# Enabled-Controller-Mini.net
KiCad netlist of a schematic drawn in EAGLE
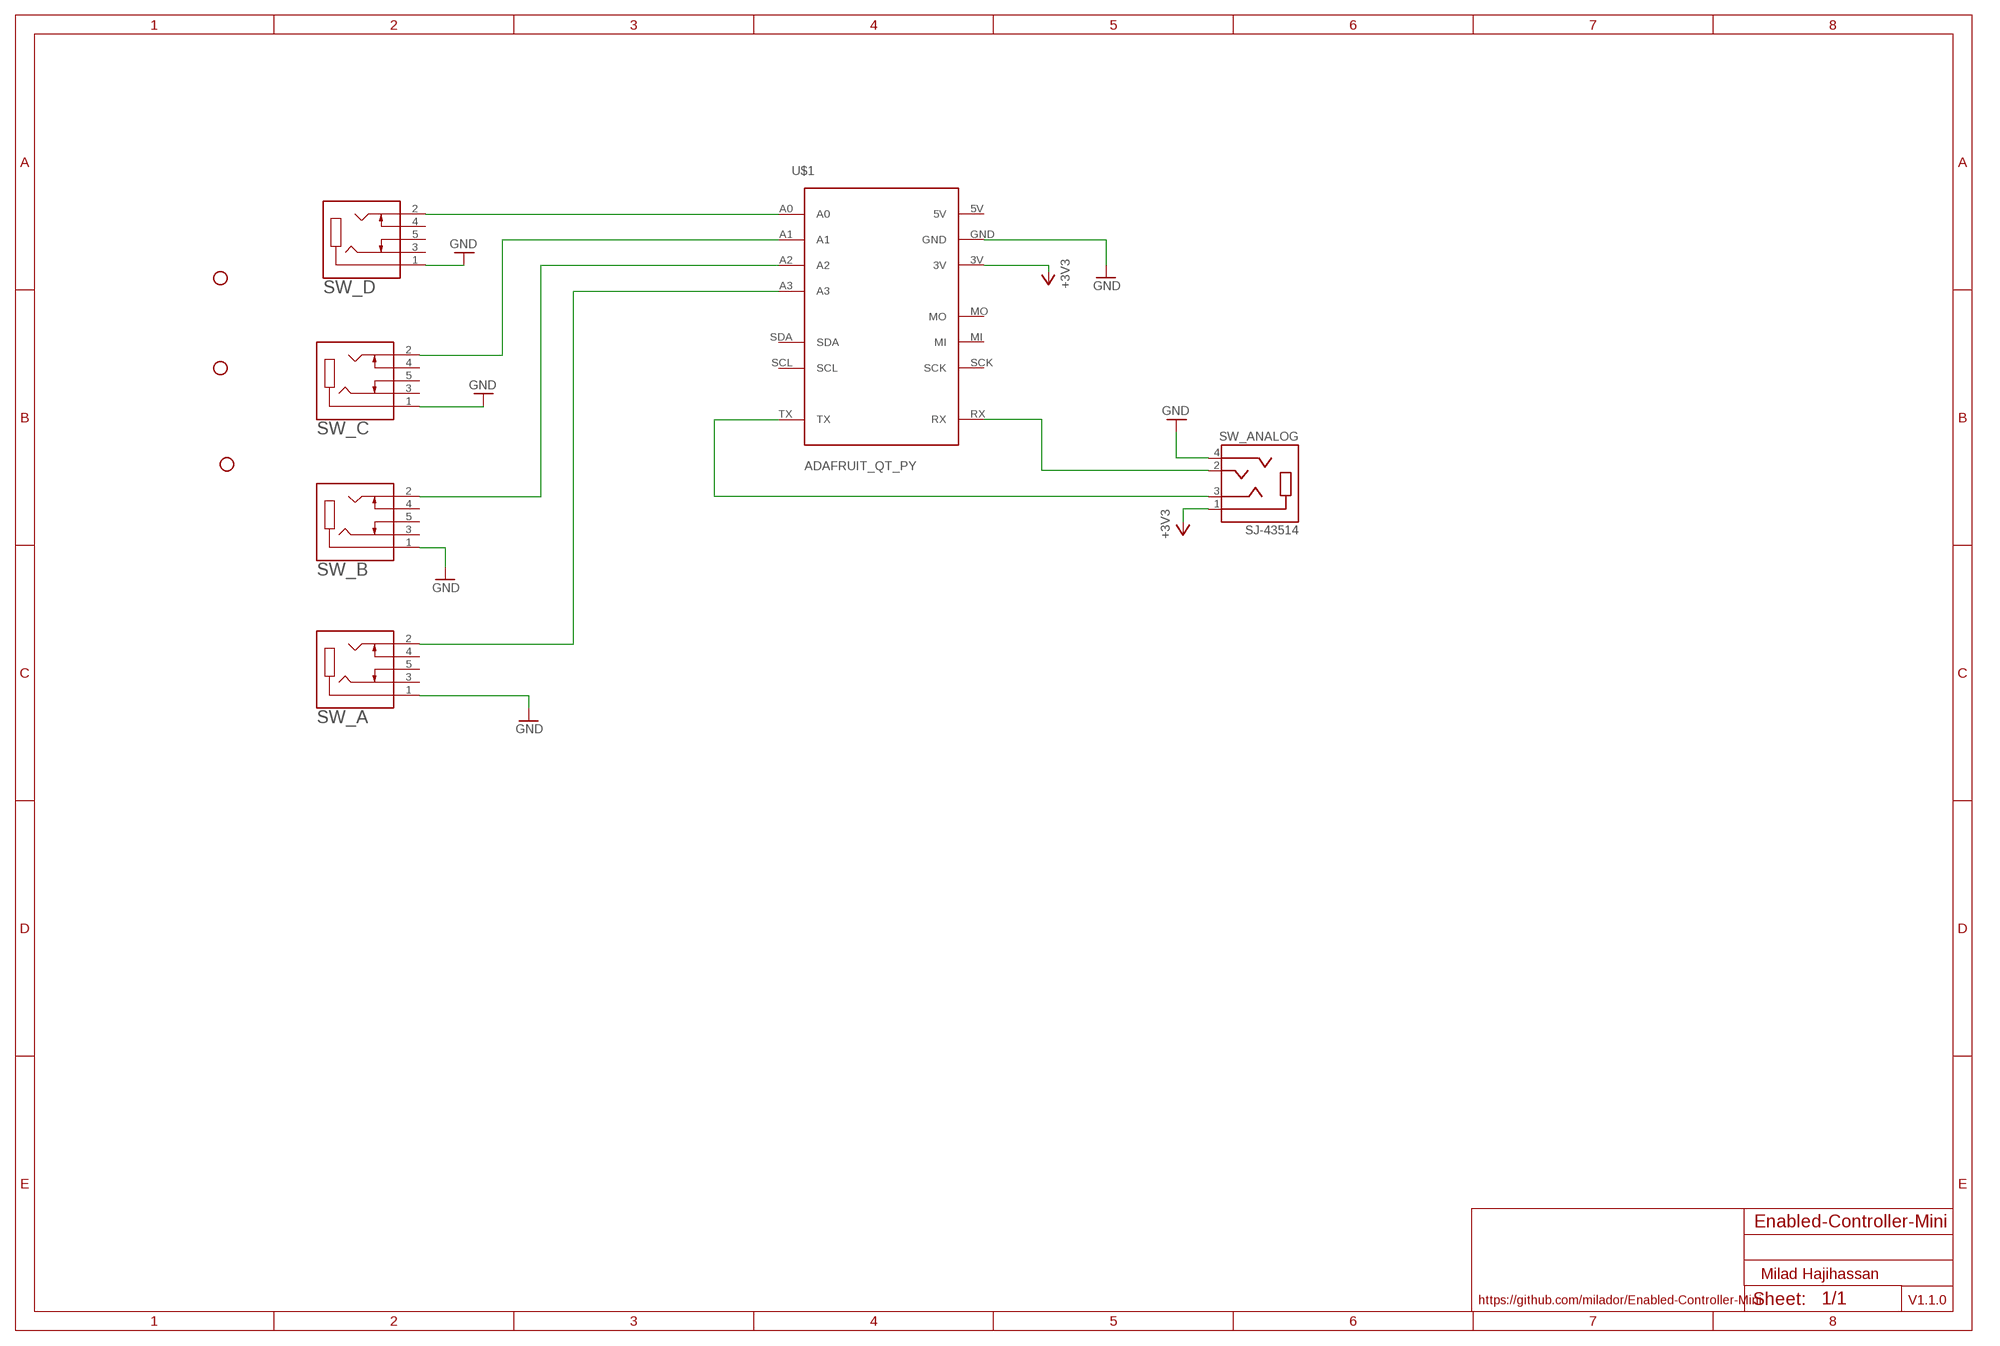
[diagram p0: schematic, sheet 1]

(export (version "E")
  (design (tool "Eeschema 10.0.6"))
  (components
    (comp (ref "STANDOFF1")
      (value "STAND-OFF-")
      (footprint "eagle-import:STAND-OFF")
      (libsource (lib "eagle-import") (part "STAND-OFF-"))
    )
    (comp (ref "STANDOFF2")
      (value "STAND-OFF-")
      (footprint "eagle-import:STAND-OFF")
      (libsource (lib "eagle-import") (part "STAND-OFF-"))
    )
    (comp (ref "STANDOFF3")
      (value "STAND-OFF-")
      (footprint "eagle-import:STAND-OFF")
      (libsource (lib "eagle-import") (part "STAND-OFF-"))
    )
    (comp (ref "SW_A")
      (value "CUI_SJ1-3535NGSJ1-3535NG")
      (footprint "eagle-import:CUI_SJ1-3535NG")
      (libsource (lib "eagle-import") (part "CUI_SJ1-3535NGSJ1-3535NG"))
    )
    (comp (ref "SW_ANALOG")
      (value "SJ-43514")
      (footprint "eagle-import:CUI_SJ-43514")
      (libsource (lib "eagle-import") (part "SJ-43514"))
    )
    (comp (ref "SW_B")
      (value "CUI_SJ1-3535NGSJ1-3535NG")
      (footprint "eagle-import:CUI_SJ1-3535NG")
      (libsource (lib "eagle-import") (part "CUI_SJ1-3535NGSJ1-3535NG"))
    )
    (comp (ref "SW_C")
      (value "CUI_SJ1-3535NGSJ1-3535NG")
      (footprint "eagle-import:CUI_SJ1-3535NG")
      (libsource (lib "eagle-import") (part "CUI_SJ1-3535NGSJ1-3535NG"))
    )
    (comp (ref "SW_D")
      (value "CUI_SJ1-3535NGSJ1-3535NG")
      (footprint "eagle-import:CUI_SJ1-3535NG")
      (libsource (lib "eagle-import") (part "CUI_SJ1-3535NGSJ1-3535NG"))
    )
    (comp (ref "U$1")
      (value "ADAFRUIT_QT_PY")
      (footprint "eagle-import:QT_PY")
      (libsource (lib "eagle-import") (part "ADAFRUIT_QT_PY"))
    )
  )
  (nets
    (net (code "1") (name "+3V3") (class "Default")
      (node (ref "SW_ANALOG") (pin "1") (pinfunction "SLEEVE_1") (pintype "passive"))
      (node (ref "U$1") (pin "3V") (pinfunction "3V_3V") (pintype "bidirectional"))
    )
    (net (code "2") (name "GND") (class "Default")
      (node (ref "SW_A") (pin "1") (pinfunction "1_1") (pintype "passive"))
      (node (ref "SW_ANALOG") (pin "4") (pinfunction "RING2_4") (pintype "passive"))
      (node (ref "SW_B") (pin "1") (pinfunction "1_1") (pintype "passive"))
      (node (ref "SW_C") (pin "1") (pinfunction "1_1") (pintype "passive"))
      (node (ref "SW_D") (pin "1") (pinfunction "1_1") (pintype "passive"))
      (node (ref "U$1") (pin "GND") (pinfunction "GND_GND") (pintype "bidirectional"))
    )
    (net (code "3") (name "Net-(SW_A-Pad2)") (class "Default")
      (node (ref "SW_A") (pin "2") (pinfunction "2_2") (pintype "passive"))
      (node (ref "U$1") (pin "A3") (pinfunction "A3_A3") (pintype "bidirectional"))
    )
    (net (code "4") (name "Net-(SW_ANALOG-RING1)") (class "Default")
      (node (ref "SW_ANALOG") (pin "3") (pinfunction "RING1_3") (pintype "passive"))
      (node (ref "U$1") (pin "TX") (pinfunction "TX_TX") (pintype "bidirectional"))
    )
    (net (code "5") (name "Net-(SW_ANALOG-TIP)") (class "Default")
      (node (ref "SW_ANALOG") (pin "2") (pinfunction "TIP_2") (pintype "passive"))
      (node (ref "U$1") (pin "RX") (pinfunction "RX_RX") (pintype "bidirectional"))
    )
    (net (code "6") (name "Net-(SW_B-Pad2)") (class "Default")
      (node (ref "SW_B") (pin "2") (pinfunction "2_2") (pintype "passive"))
      (node (ref "U$1") (pin "A2") (pinfunction "A2_A2") (pintype "bidirectional"))
    )
    (net (code "7") (name "Net-(SW_C-Pad2)") (class "Default")
      (node (ref "SW_C") (pin "2") (pinfunction "2_2") (pintype "passive"))
      (node (ref "U$1") (pin "A1") (pinfunction "A1_A1") (pintype "bidirectional"))
    )
    (net (code "8") (name "Net-(SW_D-Pad2)") (class "Default")
      (node (ref "SW_D") (pin "2") (pinfunction "2_2") (pintype "passive"))
      (node (ref "U$1") (pin "A0") (pinfunction "A0_A0") (pintype "bidirectional"))
    )
    (net (code "9") (name "unconnected-(SW_A-Pad3)") (class "Default")
      (node (ref "SW_A") (pin "3") (pinfunction "3_3") (pintype "passive"))
    )
    (net (code "10") (name "unconnected-(SW_A-Pad4)") (class "Default")
      (node (ref "SW_A") (pin "4") (pinfunction "4_4") (pintype "passive"))
    )
    (net (code "11") (name "unconnected-(SW_A-Pad5)") (class "Default")
      (node (ref "SW_A") (pin "5") (pinfunction "5_5") (pintype "passive"))
    )
    (net (code "12") (name "unconnected-(SW_B-Pad3)") (class "Default")
      (node (ref "SW_B") (pin "3") (pinfunction "3_3") (pintype "passive"))
    )
    (net (code "13") (name "unconnected-(SW_B-Pad4)") (class "Default")
      (node (ref "SW_B") (pin "4") (pinfunction "4_4") (pintype "passive"))
    )
    (net (code "14") (name "unconnected-(SW_B-Pad5)") (class "Default")
      (node (ref "SW_B") (pin "5") (pinfunction "5_5") (pintype "passive"))
    )
    (net (code "15") (name "unconnected-(SW_C-Pad3)") (class "Default")
      (node (ref "SW_C") (pin "3") (pinfunction "3_3") (pintype "passive"))
    )
    (net (code "16") (name "unconnected-(SW_C-Pad4)") (class "Default")
      (node (ref "SW_C") (pin "4") (pinfunction "4_4") (pintype "passive"))
    )
    (net (code "17") (name "unconnected-(SW_C-Pad5)") (class "Default")
      (node (ref "SW_C") (pin "5") (pinfunction "5_5") (pintype "passive"))
    )
    (net (code "18") (name "unconnected-(SW_D-Pad3)") (class "Default")
      (node (ref "SW_D") (pin "3") (pinfunction "3_3") (pintype "passive"))
    )
    (net (code "19") (name "unconnected-(SW_D-Pad4)") (class "Default")
      (node (ref "SW_D") (pin "4") (pinfunction "4_4") (pintype "passive"))
    )
    (net (code "20") (name "unconnected-(SW_D-Pad5)") (class "Default")
      (node (ref "SW_D") (pin "5") (pinfunction "5_5") (pintype "passive"))
    )
    (net (code "21") (name "unconnected-(U$1-Pad5V)") (class "Default")
      (node (ref "U$1") (pin "5V") (pinfunction "5V_5V") (pintype "bidirectional"))
    )
    (net (code "22") (name "unconnected-(U$1-PadMI)") (class "Default")
      (node (ref "U$1") (pin "MI") (pinfunction "MI_MI") (pintype "bidirectional"))
    )
    (net (code "23") (name "unconnected-(U$1-PadMO)") (class "Default")
      (node (ref "U$1") (pin "MO") (pinfunction "MO_MO") (pintype "bidirectional"))
    )
    (net (code "24") (name "unconnected-(U$1-PadSCK)") (class "Default")
      (node (ref "U$1") (pin "SCK") (pinfunction "SCK_SCK") (pintype "bidirectional"))
    )
    (net (code "25") (name "unconnected-(U$1-PadSCL)") (class "Default")
      (node (ref "U$1") (pin "SCL") (pinfunction "SCL_SCL") (pintype "bidirectional"))
    )
    (net (code "26") (name "unconnected-(U$1-PadSDA)") (class "Default")
      (node (ref "U$1") (pin "SDA") (pinfunction "SDA_SDA") (pintype "bidirectional"))
    )
  )
)
